# FPGA_PS.net
KiCad netlist of a schematic drawn in Altium Designer
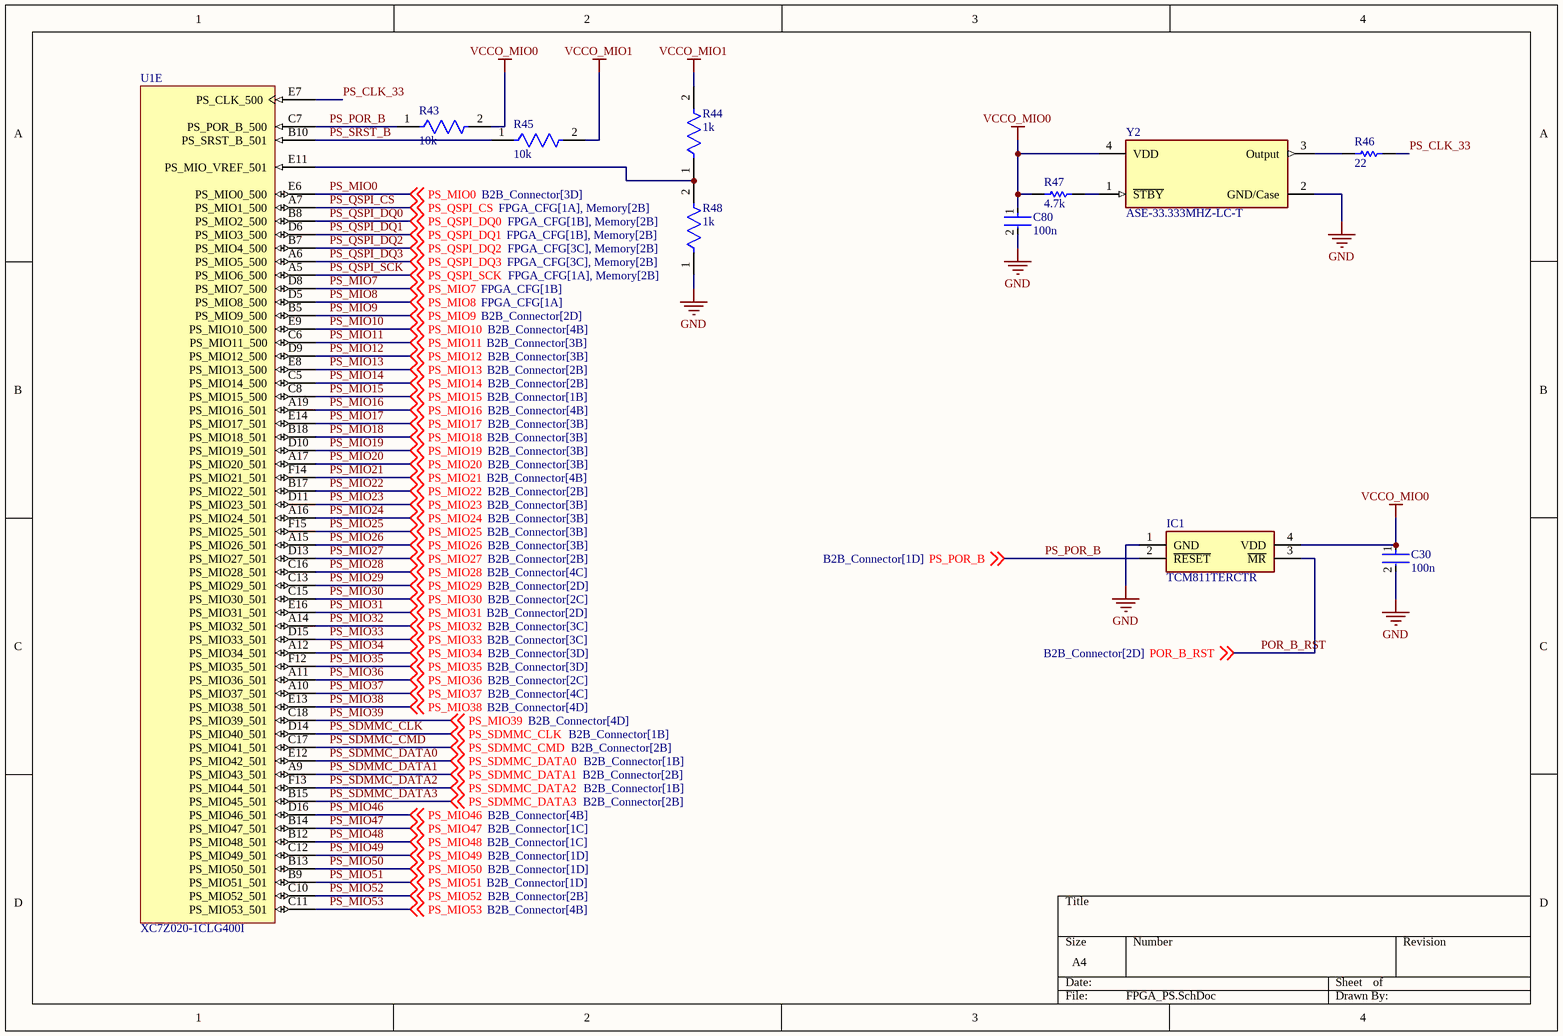
[diagram p0: FPGA_PS.SchDoc]

(export (version "E")
  (design (tool "Eeschema 10.0.6"))
  (components
    (comp (ref "C30")
      (value "100n")
      (footprint "FP-CC0603-DA-MFG")
      (description "CAP CER 0.1UF 50V X7R 0603")
      (fields (field (name "MANUFACTURER") "YAGEO") (field (name "VOLTAGE") "50 V"))
      (libsource (lib "Altium Content Vault") (part "11868f565c42a9108669ba33697ecf6"))
    )
    (comp (ref "C80")
      (value "100n")
      (footprint "FP-CC0603-DA-MFG")
      (description "CAP CER 0.1UF 50V X7R 0603")
      (fields (field (name "MANUFACTURER") "YAGEO") (field (name "VOLTAGE") "50 V"))
      (libsource (lib "Altium Content Vault") (part "11868f565c42a9108669ba33697ecf6"))
    )
    (comp (ref "IC1")
      (value "TCM811TERCTR")
      (footprint "SamacSys:TCM811TERCTR")
      (description "Integrated Circuit")
      (fields (field (name "MOUSER PART NUMBER") "579-TCM811TERCTR"))
      (libsource (lib "SamacSys") (part "TCM811TERCTR"))
    )
    (comp (ref "R43")
      (value "10k")
      (footprint "FP-RC0603-0_55-IPC_C")
      (description "RES 10K OHM 1% 1/10W 0603")
      (fields (field (name "TOLERANCE") "1%"))
      (libsource (lib "Altium Content Vault") (part "1029c3af85768c4190bb7ad29bc67b5"))
    )
    (comp (ref "R44")
      (value "1k")
      (footprint "FP-RC0603-0_55-IPC_C")
      (description "RES 1K OHM 1% 1/10W 0603")
      (fields (field (name "TOLERANCE") "1%"))
      (libsource (lib "Altium Content Vault") (part "1029c3af85768c4190bb7ad29bc67b5"))
    )
    (comp (ref "R45")
      (value "10k")
      (footprint "FP-RC0603-0_55-IPC_C")
      (description "RES 10K OHM 1% 1/10W 0603")
      (fields (field (name "TOLERANCE") "1%"))
      (libsource (lib "Altium Content Vault") (part "1029c3af85768c4190bb7ad29bc67b5"))
    )
    (comp (ref "R46")
      (value "22")
      (footprint "RESC1608X55X25NL10T15")
      (description "Chip Resistor, 22 Ohm, +/- 1%, 0.1 W, -55 to 155 degC, 0603 (1608 Metric), RoHS, Tape and Reel")
      (libsource (lib "Altium Content Vault") (part "RES-2"))
    )
    (comp (ref "R47")
      (value "4.7k")
      (footprint "RESC1608X55X25LL10T15")
      (description "Chip Resistor, 4.7 KOhm, +/- 1%, 0.1 W, -55 to 155 degC, 0603 (1608 Metric), RoHS, Tape and Reel")
      (fields (field (name "MANUFACTURER") "Yageo") (field (name "TOLERANCE") "1%"))
      (libsource (lib "Altium Content Vault") (part "RES-2"))
    )
    (comp (ref "R48")
      (value "1k")
      (footprint "FP-RC0603-0_55-IPC_C")
      (description "RES 1K OHM 1% 1/10W 0603")
      (fields (field (name "TOLERANCE") "1%"))
      (libsource (lib "Altium Content Vault") (part "1029c3af85768c4190bb7ad29bc67b5"))
    )
    (comp (ref "U1")
      (value "XC7Z020-1CLG400I")
      (footprint "CLG400")
      (fields (field (name "GENERIC PART NUMBER") "XC7Z020"))
      (libsource (lib "Altium Content Vault") (part "XNLX-XC7Z020-CLG400"))
    )
    (comp (ref "Y2")
      (value "ASE-33.333MHZ-LC-T")
      (footprint "FP-ASE-MFG")
      (description "XTAL Oscillator 33.333MHz ±50ppm CMOS 3.3V 4-SMD 3.2mm x 2.5mm")
      (libsource (lib "Altium Content Vault") (part "61a724e6190563596ac712fef61ad37"))
    )
  )
  (nets
    (net (code "1") (name "/PS_CLK_33") (class "Default")
      (node (ref "R46") (pin "2") (pinfunction "2_2") (pintype "passive"))
      (node (ref "U1") (pin "E7") (pinfunction "PS_CLK_500_E7") (pintype "input"))
    )
    (net (code "2") (name "/PS_SRST_B") (class "Default")
      (node (ref "R45") (pin "1") (pinfunction "1_1") (pintype "passive"))
      (node (ref "U1") (pin "B10") (pinfunction "PS_SRST_B_501_B10") (pintype "input"))
    )
    (net (code "3") (name "GND") (class "Default")
      (node (ref "C30") (pin "2") (pinfunction "2_2") (pintype "passive"))
      (node (ref "C80") (pin "2") (pinfunction "2_2") (pintype "passive"))
      (node (ref "IC1") (pin "1") (pinfunction "GND_1") (pintype "power_in"))
      (node (ref "R48") (pin "1") (pinfunction "1_1") (pintype "passive"))
      (node (ref "Y2") (pin "2") (pinfunction "GND/Case_2") (pintype "power_in"))
    )
    (net (code "4") (name "Net-(U1E-PS_MIO_VREF_501)") (class "Default")
      (node (ref "R44") (pin "1") (pinfunction "1_1") (pintype "passive"))
      (node (ref "R48") (pin "2") (pinfunction "2_2") (pintype "passive"))
      (node (ref "U1") (pin "E11") (pinfunction "PS_MIO_VREF_501_E11") (pintype "input"))
    )
    (net (code "5") (name "Net-(Y2-Output)") (class "Default")
      (node (ref "R46") (pin "1") (pinfunction "1_1") (pintype "passive"))
      (node (ref "Y2") (pin "3") (pinfunction "Output_3") (pintype "output"))
    )
    (net (code "6") (name "Net-(Y2-~{STBY})") (class "Default")
      (node (ref "R47") (pin "2") (pinfunction "2_2") (pintype "passive"))
      (node (ref "Y2") (pin "1") (pinfunction "~{STBY}_1") (pintype "input"))
    )
    (net (code "7") (name "POR_B_RST") (class "Default")
      (node (ref "IC1") (pin "3") (pinfunction "~{MR}_3") (pintype "passive"))
    )
    (net (code "8") (name "PS_MIO0") (class "Default")
      (node (ref "U1") (pin "E6") (pinfunction "PS_MIO0_500_E6") (pintype "bidirectional"))
    )
    (net (code "9") (name "PS_MIO7") (class "Default")
      (node (ref "U1") (pin "D8") (pinfunction "PS_MIO7_500_D8") (pintype "bidirectional"))
    )
    (net (code "10") (name "PS_MIO8") (class "Default")
      (node (ref "U1") (pin "D5") (pinfunction "PS_MIO8_500_D5") (pintype "bidirectional"))
    )
    (net (code "11") (name "PS_MIO9") (class "Default")
      (node (ref "U1") (pin "B5") (pinfunction "PS_MIO9_500_B5") (pintype "bidirectional"))
    )
    (net (code "12") (name "PS_MIO10") (class "Default")
      (node (ref "U1") (pin "E9") (pinfunction "PS_MIO10_500_E9") (pintype "bidirectional"))
    )
    (net (code "13") (name "PS_MIO11") (class "Default")
      (node (ref "U1") (pin "C6") (pinfunction "PS_MIO11_500_C6") (pintype "bidirectional"))
    )
    (net (code "14") (name "PS_MIO12") (class "Default")
      (node (ref "U1") (pin "D9") (pinfunction "PS_MIO12_500_D9") (pintype "bidirectional"))
    )
    (net (code "15") (name "PS_MIO13") (class "Default")
      (node (ref "U1") (pin "E8") (pinfunction "PS_MIO13_500_E8") (pintype "bidirectional"))
    )
    (net (code "16") (name "PS_MIO14") (class "Default")
      (node (ref "U1") (pin "C5") (pinfunction "PS_MIO14_500_C5") (pintype "bidirectional"))
    )
    (net (code "17") (name "PS_MIO15") (class "Default")
      (node (ref "U1") (pin "C8") (pinfunction "PS_MIO15_500_C8") (pintype "bidirectional"))
    )
    (net (code "18") (name "PS_MIO16") (class "Default")
      (node (ref "U1") (pin "A19") (pinfunction "PS_MIO16_501_A19") (pintype "bidirectional"))
    )
    (net (code "19") (name "PS_MIO17") (class "Default")
      (node (ref "U1") (pin "E14") (pinfunction "PS_MIO17_501_E14") (pintype "bidirectional"))
    )
    (net (code "20") (name "PS_MIO18") (class "Default")
      (node (ref "U1") (pin "B18") (pinfunction "PS_MIO18_501_B18") (pintype "bidirectional"))
    )
    (net (code "21") (name "PS_MIO19") (class "Default")
      (node (ref "U1") (pin "D10") (pinfunction "PS_MIO19_501_D10") (pintype "bidirectional"))
    )
    (net (code "22") (name "PS_MIO20") (class "Default")
      (node (ref "U1") (pin "A17") (pinfunction "PS_MIO20_501_A17") (pintype "bidirectional"))
    )
    (net (code "23") (name "PS_MIO21") (class "Default")
      (node (ref "U1") (pin "F14") (pinfunction "PS_MIO21_501_F14") (pintype "bidirectional"))
    )
    (net (code "24") (name "PS_MIO22") (class "Default")
      (node (ref "U1") (pin "B17") (pinfunction "PS_MIO22_501_B17") (pintype "bidirectional"))
    )
    (net (code "25") (name "PS_MIO23") (class "Default")
      (node (ref "U1") (pin "D11") (pinfunction "PS_MIO23_501_D11") (pintype "bidirectional"))
    )
    (net (code "26") (name "PS_MIO24") (class "Default")
      (node (ref "U1") (pin "A16") (pinfunction "PS_MIO24_501_A16") (pintype "bidirectional"))
    )
    (net (code "27") (name "PS_MIO25") (class "Default")
      (node (ref "U1") (pin "F15") (pinfunction "PS_MIO25_501_F15") (pintype "bidirectional"))
    )
    (net (code "28") (name "PS_MIO26") (class "Default")
      (node (ref "U1") (pin "A15") (pinfunction "PS_MIO26_501_A15") (pintype "bidirectional"))
    )
    (net (code "29") (name "PS_MIO27") (class "Default")
      (node (ref "U1") (pin "D13") (pinfunction "PS_MIO27_501_D13") (pintype "bidirectional"))
    )
    (net (code "30") (name "PS_MIO28") (class "Default")
      (node (ref "U1") (pin "C16") (pinfunction "PS_MIO28_501_C16") (pintype "bidirectional"))
    )
    (net (code "31") (name "PS_MIO29") (class "Default")
      (node (ref "U1") (pin "C13") (pinfunction "PS_MIO29_501_C13") (pintype "bidirectional"))
    )
    (net (code "32") (name "PS_MIO30") (class "Default")
      (node (ref "U1") (pin "C15") (pinfunction "PS_MIO30_501_C15") (pintype "bidirectional"))
    )
    (net (code "33") (name "PS_MIO31") (class "Default")
      (node (ref "U1") (pin "E16") (pinfunction "PS_MIO31_501_E16") (pintype "bidirectional"))
    )
    (net (code "34") (name "PS_MIO32") (class "Default")
      (node (ref "U1") (pin "A14") (pinfunction "PS_MIO32_501_A14") (pintype "bidirectional"))
    )
    (net (code "35") (name "PS_MIO33") (class "Default")
      (node (ref "U1") (pin "D15") (pinfunction "PS_MIO33_501_D15") (pintype "bidirectional"))
    )
    (net (code "36") (name "PS_MIO34") (class "Default")
      (node (ref "U1") (pin "A12") (pinfunction "PS_MIO34_501_A12") (pintype "bidirectional"))
    )
    (net (code "37") (name "PS_MIO35") (class "Default")
      (node (ref "U1") (pin "F12") (pinfunction "PS_MIO35_501_F12") (pintype "bidirectional"))
    )
    (net (code "38") (name "PS_MIO36") (class "Default")
      (node (ref "U1") (pin "A11") (pinfunction "PS_MIO36_501_A11") (pintype "bidirectional"))
    )
    (net (code "39") (name "PS_MIO37") (class "Default")
      (node (ref "U1") (pin "A10") (pinfunction "PS_MIO37_501_A10") (pintype "bidirectional"))
    )
    (net (code "40") (name "PS_MIO38") (class "Default")
      (node (ref "U1") (pin "E13") (pinfunction "PS_MIO38_501_E13") (pintype "bidirectional"))
    )
    (net (code "41") (name "PS_MIO39") (class "Default")
      (node (ref "U1") (pin "C18") (pinfunction "PS_MIO39_501_C18") (pintype "bidirectional"))
    )
    (net (code "42") (name "PS_MIO46") (class "Default")
      (node (ref "U1") (pin "D16") (pinfunction "PS_MIO46_501_D16") (pintype "bidirectional"))
    )
    (net (code "43") (name "PS_MIO47") (class "Default")
      (node (ref "U1") (pin "B14") (pinfunction "PS_MIO47_501_B14") (pintype "bidirectional"))
    )
    (net (code "44") (name "PS_MIO48") (class "Default")
      (node (ref "U1") (pin "B12") (pinfunction "PS_MIO48_501_B12") (pintype "bidirectional"))
    )
    (net (code "45") (name "PS_MIO49") (class "Default")
      (node (ref "U1") (pin "C12") (pinfunction "PS_MIO49_501_C12") (pintype "bidirectional"))
    )
    (net (code "46") (name "PS_MIO50") (class "Default")
      (node (ref "U1") (pin "B13") (pinfunction "PS_MIO50_501_B13") (pintype "bidirectional"))
    )
    (net (code "47") (name "PS_MIO51") (class "Default")
      (node (ref "U1") (pin "B9") (pinfunction "PS_MIO51_501_B9") (pintype "bidirectional"))
    )
    (net (code "48") (name "PS_MIO52") (class "Default")
      (node (ref "U1") (pin "C10") (pinfunction "PS_MIO52_501_C10") (pintype "bidirectional"))
    )
    (net (code "49") (name "PS_MIO53") (class "Default")
      (node (ref "U1") (pin "C11") (pinfunction "PS_MIO53_501_C11") (pintype "bidirectional"))
    )
    (net (code "50") (name "PS_POR_B") (class "Default")
      (node (ref "IC1") (pin "2") (pinfunction "~{RESET}_2") (pintype "passive"))
      (node (ref "R43") (pin "1") (pinfunction "1_1") (pintype "passive"))
      (node (ref "U1") (pin "C7") (pinfunction "PS_POR_B_500_C7") (pintype "input"))
    )
    (net (code "51") (name "PS_QSPI_CS") (class "Default")
      (node (ref "U1") (pin "A7") (pinfunction "PS_MIO1_500_A7") (pintype "bidirectional"))
    )
    (net (code "52") (name "PS_QSPI_DQ0") (class "Default")
      (node (ref "U1") (pin "B8") (pinfunction "PS_MIO2_500_B8") (pintype "bidirectional"))
    )
    (net (code "53") (name "PS_QSPI_DQ1") (class "Default")
      (node (ref "U1") (pin "D6") (pinfunction "PS_MIO3_500_D6") (pintype "bidirectional"))
    )
    (net (code "54") (name "PS_QSPI_DQ2") (class "Default")
      (node (ref "U1") (pin "B7") (pinfunction "PS_MIO4_500_B7") (pintype "bidirectional"))
    )
    (net (code "55") (name "PS_QSPI_DQ3") (class "Default")
      (node (ref "U1") (pin "A6") (pinfunction "PS_MIO5_500_A6") (pintype "bidirectional"))
    )
    (net (code "56") (name "PS_QSPI_SCK") (class "Default")
      (node (ref "U1") (pin "A5") (pinfunction "PS_MIO6_500_A5") (pintype "bidirectional"))
    )
    (net (code "57") (name "PS_SDMMC_CLK") (class "Default")
      (node (ref "U1") (pin "D14") (pinfunction "PS_MIO40_501_D14") (pintype "bidirectional"))
    )
    (net (code "58") (name "PS_SDMMC_CMD") (class "Default")
      (node (ref "U1") (pin "C17") (pinfunction "PS_MIO41_501_C17") (pintype "bidirectional"))
    )
    (net (code "59") (name "PS_SDMMC_DATA0") (class "Default")
      (node (ref "U1") (pin "E12") (pinfunction "PS_MIO42_501_E12") (pintype "bidirectional"))
    )
    (net (code "60") (name "PS_SDMMC_DATA1") (class "Default")
      (node (ref "U1") (pin "A9") (pinfunction "PS_MIO43_501_A9") (pintype "bidirectional"))
    )
    (net (code "61") (name "PS_SDMMC_DATA2") (class "Default")
      (node (ref "U1") (pin "F13") (pinfunction "PS_MIO44_501_F13") (pintype "bidirectional"))
    )
    (net (code "62") (name "PS_SDMMC_DATA3") (class "Default")
      (node (ref "U1") (pin "B15") (pinfunction "PS_MIO45_501_B15") (pintype "bidirectional"))
    )
    (net (code "63") (name "VCCO_MIO0") (class "Default")
      (node (ref "C30") (pin "1") (pinfunction "1_1") (pintype "passive"))
      (node (ref "C80") (pin "1") (pinfunction "1_1") (pintype "passive"))
      (node (ref "IC1") (pin "4") (pinfunction "VDD_4") (pintype "power_in"))
      (node (ref "R43") (pin "2") (pinfunction "2_2") (pintype "passive"))
      (node (ref "R47") (pin "1") (pinfunction "1_1") (pintype "passive"))
      (node (ref "Y2") (pin "4") (pinfunction "VDD_4") (pintype "power_in"))
    )
    (net (code "64") (name "VCCO_MIO1") (class "Default")
      (node (ref "R44") (pin "2") (pinfunction "2_2") (pintype "passive"))
      (node (ref "R45") (pin "2") (pinfunction "2_2") (pintype "passive"))
    )
  )
)
